# LTC3119_Buck_Boost_Converter.net
KiCad netlist of a schematic drawn in Altium Designer
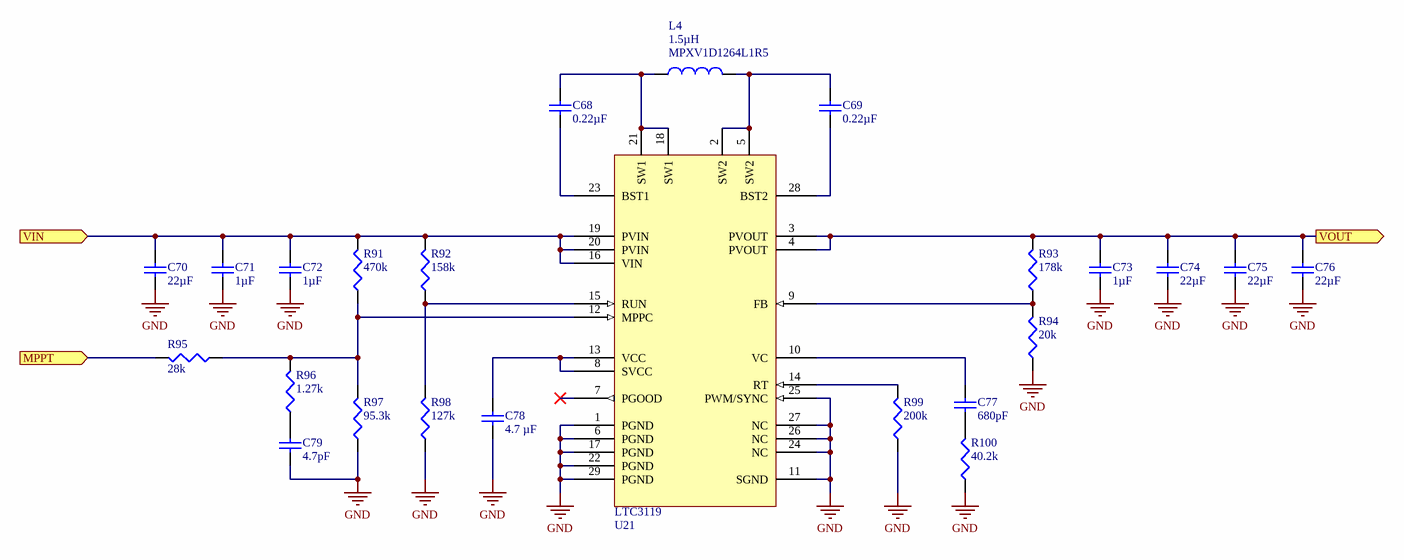
[diagram p0: LTC3119 Buck Boost Converter.SchDoc]

(export (version "E")
  (design (tool "Eeschema 10.0.6"))
  (components
    (comp (ref "C68")
      (value "0.22µF")
      (footprint "TDK-CGA3E")
      (description "CAP CER 0.22UF 50V X7R 0603")
      (fields
        (field (name "PART NUMBER") "PC-TDK-02393")
        (field (name "MANUFACTURER PART NUMBER") "CGA3E3X7R1H224K080AB")
        (field (name "PUBLISHER") "AlbertaSat")
      )
      (libsource (lib "Database") (part "Cap"))
    )
    (comp (ref "C69")
      (value "0.22µF")
      (footprint "TDK-CGA3E")
      (description "CAP CER 0.22UF 50V X7R 0603")
      (fields
        (field (name "PART NUMBER") "PC-TDK-02393")
        (field (name "MANUFACTURER PART NUMBER") "CGA3E3X7R1H224K080AB")
        (field (name "PUBLISHER") "AlbertaSat")
      )
      (libsource (lib "Database") (part "Cap"))
    )
    (comp (ref "C70")
      (value "22µF")
      (footprint "TDK-C3225")
      (description "CAP CER 22UF 25V X7R 1210")
      (fields
        (field (name "PART NUMBER") "PC-TDK-02965")
        (field (name "MANUFACTURER PART NUMBER") "C3225X7R1E226M250AB")
        (field (name "PUBLISHER") "AlbertaSat")
      )
      (libsource (lib "Database") (part "Cap"))
    )
    (comp (ref "C71")
      (value "1µF")
      (footprint "TY-0603A")
      (description "CAP CER 1UF 50V X7R 0603")
      (fields
        (field (name "PART NUMBER") "PC-TY-00404")
        (field (name "MANUFACTURER PART NUMBER") "UMK107AB7105KA-T")
        (field (name "PUBLISHER") "AlbertaSat")
      )
      (libsource (lib "Database") (part "Cap"))
    )
    (comp (ref "C72")
      (value "1µF")
      (footprint "TY-0603A")
      (description "CAP CER 1UF 50V X7R 0603")
      (fields
        (field (name "PART NUMBER") "PC-TY-00404")
        (field (name "MANUFACTURER PART NUMBER") "UMK107AB7105KA-T")
        (field (name "PUBLISHER") "AlbertaSat")
      )
      (libsource (lib "Database") (part "Cap"))
    )
    (comp (ref "C73")
      (value "1µF")
      (footprint "TY-0603A")
      (description "CAP CER 1UF 50V X7R 0603")
      (fields
        (field (name "PART NUMBER") "PC-TY-00404")
        (field (name "MANUFACTURER PART NUMBER") "UMK107AB7105KA-T")
        (field (name "PUBLISHER") "AlbertaSat")
      )
      (libsource (lib "Database") (part "Cap"))
    )
    (comp (ref "C74")
      (value "22µF")
      (footprint "TDK-C3225")
      (description "CAP CER 22UF 25V X7R 1210")
      (fields
        (field (name "PART NUMBER") "PC-TDK-02965")
        (field (name "MANUFACTURER PART NUMBER") "C3225X7R1E226M250AB")
        (field (name "PUBLISHER") "AlbertaSat")
      )
      (libsource (lib "Database") (part "Cap"))
    )
    (comp (ref "C75")
      (value "22µF")
      (footprint "TDK-C3225")
      (description "CAP CER 22UF 25V X7R 1210")
      (fields
        (field (name "PART NUMBER") "PC-TDK-02965")
        (field (name "MANUFACTURER PART NUMBER") "C3225X7R1E226M250AB")
        (field (name "PUBLISHER") "AlbertaSat")
      )
      (libsource (lib "Database") (part "Cap"))
    )
    (comp (ref "C76")
      (value "22µF")
      (footprint "TDK-C3225")
      (description "CAP CER 22UF 25V X7R 1210")
      (fields
        (field (name "PART NUMBER") "PC-TDK-02965")
        (field (name "MANUFACTURER PART NUMBER") "C3225X7R1E226M250AB")
        (field (name "PUBLISHER") "AlbertaSat")
      )
      (libsource (lib "Database") (part "Cap"))
    )
    (comp (ref "C77")
      (value "680pF")
      (footprint "TDK-CGA2B")
      (description "CAP CER 680PF 100V C0G 0402")
      (fields
        (field (name "PART NUMBER") "PC-TDK-01417")
        (field (name "MANUFACTURER PART NUMBER") "CGA2B1C0G2A681J050BC")
        (field (name "PUBLISHER") "AlbertaSat")
      )
      (libsource (lib "Database") (part "Cap"))
    )
    (comp (ref "C78")
      (value "4.7 µF")
      (footprint "MUR-GRM188")
      (description "CAP CER 4.7UF 16V X7R 0603")
      (fields
        (field (name "PART NUMBER") "10165")
        (field (name "MANUFACTURER PART NUMBER") "GRM188Z71C475KE21D")
        (field (name "PUBLISHER") "Altium Limited")
      )
      (libsource (lib "Database") (part "Cap"))
    )
    (comp (ref "C79")
      (value "4.7pF")
      (footprint "TDK-CGA2B")
      (description "CAP CER 4.7PF 50V NP0 0402")
      (fields
        (field (name "PART NUMBER") "PC-TDK-01056")
        (field (name "MANUFACTURER PART NUMBER") "CGA2B2NP01H4R7C050BA")
        (field (name "PUBLISHER") "AlbertaSat")
      )
      (libsource (lib "Database") (part "Cap"))
    )
    (comp (ref "L4")
      (value "1.5µH")
      (footprint "KEM-MPXV1D1264L100")
      (description "FIXED IND 1.5UH 28.8A 2.9MOHM SM")
      (fields
        (field (name "PART NUMBER") "PL-KEM-03168")
        (field (name "MANUFACTURER PART NUMBER") "MPXV1D1264L1R5")
        (field (name "TOLERANCE") "±20%")
        (field (name "PUBLISHER") "AlbertaSat")
      )
      (libsource (lib "Database") (part "Inductor"))
    )
    (comp (ref "R91")
      (value "470k")
      (footprint "VSH-0402MCS")
      (description "RES 470K OHM 0.1% 1/16W 0402")
      (fields
        (field (name "PART NUMBER") "PR-VSH-00330")
        (field (name "MANUFACTURER PART NUMBER") "MCS0402MD4703BE000")
        (field (name "PUBLISHER") "AlbertaSat")
      )
      (libsource (lib "Database") (part "Res3"))
    )
    (comp (ref "R92")
      (value "158k")
      (footprint "TEC-RP731E")
      (description "RES 158K OHM 0.1% 1/10W 0402")
      (fields
        (field (name "PART NUMBER") "905")
        (field (name "MANUFACTURER PART NUMBER") "RP73PF1E158KBTD")
        (field (name "PUBLISHER") "Altium Limited")
      )
      (libsource (lib "Database") (part "Res3"))
    )
    (comp (ref "R93")
      (value "178k")
      (footprint "TEC-RP731E")
      (description "RES 178K OHM 0.1% 1/10W 0402")
      (fields
        (field (name "PART NUMBER") "910")
        (field (name "MANUFACTURER PART NUMBER") "RP73PF1E178KBTD")
        (field (name "PUBLISHER") "Altium Limited")
      )
      (libsource (lib "Database") (part "Res3"))
    )
    (comp (ref "R94")
      (value "20k")
      (footprint "TEC-RP731E")
      (description "RES 20K OHM 0.1% 1/10W 0402")
      (fields
        (field (name "PART NUMBER") "819")
        (field (name "MANUFACTURER PART NUMBER") "RP73PF1E20KBTD")
        (field (name "PUBLISHER") "Altium Limited")
      )
      (libsource (lib "Database") (part "Res3"))
    )
    (comp (ref "R95")
      (value "28k")
      (footprint "TEC-RP731E")
      (description "RES 28K OHM 0.1% 1/10W 0402")
      (fields
        (field (name "PART NUMBER") "833")
        (field (name "MANUFACTURER PART NUMBER") "RP73PF1E28KBTD")
        (field (name "PUBLISHER") "Altium Limited")
      )
      (libsource (lib "Database") (part "Res3"))
    )
    (comp (ref "R96")
      (value "1.27k")
      (footprint "TEC-RP731E")
      (description "RES 1.27K OHM 0.1% 1/10W 0402")
      (fields
        (field (name "PART NUMBER") "704")
        (field (name "MANUFACTURER PART NUMBER") "RP73PF1E1K27BTD")
        (field (name "PUBLISHER") "Altium Limited")
      )
      (libsource (lib "Database") (part "Res3"))
    )
    (comp (ref "R97")
      (value "95.3k")
      (footprint "TEC-RP731E")
      (description "RES 95.3K OHM 0.1% 1/10W 0402")
      (fields
        (field (name "PART NUMBER") "884")
        (field (name "MANUFACTURER PART NUMBER") "RP73PF1E95K3BTD")
        (field (name "PUBLISHER") "Altium Limited")
      )
      (libsource (lib "Database") (part "Res3"))
    )
    (comp (ref "R98")
      (value "127k")
      (footprint "TEC-RP731E")
      (description "RES 127K OHM 0.1% 1/10W 0402")
      (fields
        (field (name "PART NUMBER") "896")
        (field (name "MANUFACTURER PART NUMBER") "RP73PF1E127KBTD")
        (field (name "PUBLISHER") "Altium Limited")
      )
      (libsource (lib "Database") (part "Res3"))
    )
    (comp (ref "R99")
      (value "200k")
      (footprint "TEC-RP731E")
      (description "RES 200K OHM 0.1% 1/10W 0402")
      (fields
        (field (name "PART NUMBER") "915")
        (field (name "MANUFACTURER PART NUMBER") "RP73PF1E200KBTD")
        (field (name "PUBLISHER") "Altium Limited")
      )
      (libsource (lib "Database") (part "Res3"))
    )
    (comp (ref "R100")
      (value "40.2k")
      (footprint "TEC-RP731E")
      (description "RES 40.2K OHM 0.1% 1/10W 0402")
      (fields
        (field (name "PART NUMBER") "848")
        (field (name "MANUFACTURER PART NUMBER") "RP73PF1E40K2BTD")
        (field (name "PUBLISHER") "Altium Limited")
      )
      (libsource (lib "Database") (part "Res3"))
    )
    (comp (ref "U21")
      (value "LTC3119")
      (footprint "LT-05-08-1712C")
      (description "IC REG BCK BST ADJ 5A 28QFN")
      (fields
        (field (name "PART NUMBER") "PU-LTC-00059")
        (field (name "MANUFACTURER PART NUMBER") "LTC3119IUFD#PBF")
        (field (name "PUBLISHER") "AlbertaSat")
      )
      (libsource (lib "Database") (part "LTC3119xUFD"))
    )
  )
  (nets
    (net (code "1") (name "/MPPT") (class "Default")
      (node (ref "R95") (pin "2") (pinfunction "2_2") (pintype "passive"))
    )
    (net (code "2") (name "/VIN") (class "Default")
      (node (ref "C70") (pin "2") (pinfunction "2_2") (pintype "passive"))
      (node (ref "C71") (pin "2") (pinfunction "2_2") (pintype "passive"))
      (node (ref "C72") (pin "2") (pinfunction "2_2") (pintype "passive"))
      (node (ref "R91") (pin "2") (pinfunction "2_2") (pintype "passive"))
      (node (ref "R92") (pin "2") (pinfunction "2_2") (pintype "passive"))
      (node (ref "U21") (pin "16") (pinfunction "VIN_16") (pintype "power_in"))
      (node (ref "U21") (pin "19") (pinfunction "PVIN_19") (pintype "power_in"))
      (node (ref "U21") (pin "20") (pinfunction "PVIN_20") (pintype "power_in"))
    )
    (net (code "3") (name "/VOUT") (class "Default")
      (node (ref "C73") (pin "2") (pinfunction "2_2") (pintype "passive"))
      (node (ref "C74") (pin "2") (pinfunction "2_2") (pintype "passive"))
      (node (ref "C75") (pin "2") (pinfunction "2_2") (pintype "passive"))
      (node (ref "C76") (pin "2") (pinfunction "2_2") (pintype "passive"))
      (node (ref "R93") (pin "2") (pinfunction "2_2") (pintype "passive"))
      (node (ref "U21") (pin "3") (pinfunction "PVOUT_3") (pintype "power_in"))
      (node (ref "U21") (pin "4") (pinfunction "PVOUT_4") (pintype "power_in"))
    )
    (net (code "4") (name "GND") (class "Default")
      (node (ref "C70") (pin "1") (pinfunction "1_1") (pintype "passive"))
      (node (ref "C71") (pin "1") (pinfunction "1_1") (pintype "passive"))
      (node (ref "C72") (pin "1") (pinfunction "1_1") (pintype "passive"))
      (node (ref "C73") (pin "1") (pinfunction "1_1") (pintype "passive"))
      (node (ref "C74") (pin "1") (pinfunction "1_1") (pintype "passive"))
      (node (ref "C75") (pin "1") (pinfunction "1_1") (pintype "passive"))
      (node (ref "C76") (pin "1") (pinfunction "1_1") (pintype "passive"))
      (node (ref "C78") (pin "1") (pinfunction "1_1") (pintype "passive"))
      (node (ref "C79") (pin "1") (pinfunction "1_1") (pintype "passive"))
      (node (ref "R100") (pin "1") (pinfunction "1_1") (pintype "passive"))
      (node (ref "R94") (pin "1") (pinfunction "1_1") (pintype "passive"))
      (node (ref "R97") (pin "1") (pinfunction "1_1") (pintype "passive"))
      (node (ref "R98") (pin "1") (pinfunction "1_1") (pintype "passive"))
      (node (ref "R99") (pin "1") (pinfunction "1_1") (pintype "passive"))
      (node (ref "U21") (pin "1") (pinfunction "PGND_1") (pintype "power_in"))
      (node (ref "U21") (pin "11") (pinfunction "SGND_11") (pintype "power_in"))
      (node (ref "U21") (pin "17") (pinfunction "PGND_17") (pintype "power_in"))
      (node (ref "U21") (pin "22") (pinfunction "PGND_22") (pintype "power_in"))
      (node (ref "U21") (pin "24") (pinfunction "NC_24") (pintype "passive"))
      (node (ref "U21") (pin "25") (pinfunction "PWM/SYNC_25") (pintype "input"))
      (node (ref "U21") (pin "26") (pinfunction "NC_26") (pintype "passive"))
      (node (ref "U21") (pin "27") (pinfunction "NC_27") (pintype "passive"))
      (node (ref "U21") (pin "29") (pinfunction "PGND_29") (pintype "power_in"))
      (node (ref "U21") (pin "6") (pinfunction "PGND_6") (pintype "power_in"))
    )
    (net (code "5") (name "Net-(C68-Pad2)") (class "Default")
      (node (ref "C68") (pin "2") (pinfunction "2_2") (pintype "passive"))
      (node (ref "L4") (pin "1") (pinfunction "1_1") (pintype "passive"))
      (node (ref "U21") (pin "18") (pinfunction "SW1_18") (pintype "power_in"))
      (node (ref "U21") (pin "21") (pinfunction "SW1_21") (pintype "power_in"))
    )
    (net (code "6") (name "Net-(C69-Pad2)") (class "Default")
      (node (ref "C69") (pin "2") (pinfunction "2_2") (pintype "passive"))
      (node (ref "L4") (pin "2") (pinfunction "2_2") (pintype "passive"))
      (node (ref "U21") (pin "2") (pinfunction "SW2_2") (pintype "power_in"))
      (node (ref "U21") (pin "5") (pinfunction "SW2_5") (pintype "power_in"))
    )
    (net (code "7") (name "Net-(C77-Pad1)") (class "Default")
      (node (ref "C77") (pin "1") (pinfunction "1_1") (pintype "passive"))
      (node (ref "R100") (pin "2") (pinfunction "2_2") (pintype "passive"))
    )
    (net (code "8") (name "Net-(C79-Pad2)") (class "Default")
      (node (ref "C79") (pin "2") (pinfunction "2_2") (pintype "passive"))
      (node (ref "R96") (pin "1") (pinfunction "1_1") (pintype "passive"))
    )
    (net (code "9") (name "Net-(U21-BST1)") (class "Default")
      (node (ref "C68") (pin "1") (pinfunction "1_1") (pintype "passive"))
      (node (ref "U21") (pin "23") (pinfunction "BST1_23") (pintype "power_in"))
    )
    (net (code "10") (name "Net-(U21-BST2)") (class "Default")
      (node (ref "C69") (pin "1") (pinfunction "1_1") (pintype "passive"))
      (node (ref "U21") (pin "28") (pinfunction "BST2_28") (pintype "power_in"))
    )
    (net (code "11") (name "Net-(U21-FB)") (class "Default")
      (node (ref "R93") (pin "1") (pinfunction "1_1") (pintype "passive"))
      (node (ref "R94") (pin "2") (pinfunction "2_2") (pintype "passive"))
      (node (ref "U21") (pin "9") (pinfunction "FB_9") (pintype "input"))
    )
    (net (code "12") (name "Net-(U21-MPPC)") (class "Default")
      (node (ref "R91") (pin "1") (pinfunction "1_1") (pintype "passive"))
      (node (ref "R95") (pin "1") (pinfunction "1_1") (pintype "passive"))
      (node (ref "R96") (pin "2") (pinfunction "2_2") (pintype "passive"))
      (node (ref "R97") (pin "2") (pinfunction "2_2") (pintype "passive"))
      (node (ref "U21") (pin "12") (pinfunction "MPPC_12") (pintype "input"))
    )
    (net (code "13") (name "Net-(U21-RT)") (class "Default")
      (node (ref "R99") (pin "2") (pinfunction "2_2") (pintype "passive"))
      (node (ref "U21") (pin "14") (pinfunction "RT_14") (pintype "input"))
    )
    (net (code "14") (name "Net-(U21-RUN)") (class "Default")
      (node (ref "R92") (pin "1") (pinfunction "1_1") (pintype "passive"))
      (node (ref "R98") (pin "2") (pinfunction "2_2") (pintype "passive"))
      (node (ref "U21") (pin "15") (pinfunction "RUN_15") (pintype "input"))
    )
    (net (code "15") (name "Net-(U21-SVCC)") (class "Default")
      (node (ref "C78") (pin "2") (pinfunction "2_2") (pintype "passive"))
      (node (ref "U21") (pin "13") (pinfunction "VCC_13") (pintype "power_in"))
      (node (ref "U21") (pin "8") (pinfunction "SVCC_8") (pintype "power_in"))
    )
    (net (code "16") (name "Net-(U21-VC)") (class "Default")
      (node (ref "C77") (pin "2") (pinfunction "2_2") (pintype "passive"))
      (node (ref "U21") (pin "10") (pinfunction "VC_10") (pintype "power_in"))
    )
    (net (code "17") (name "unconnected-(U21-PGOOD-Pad7)") (class "Default")
      (node (ref "U21") (pin "7") (pinfunction "PGOOD_7") (pintype "output+no_connect"))
    )
  )
)
